# merch-hat.net
KiCad netlist of a schematic drawn in EAGLE
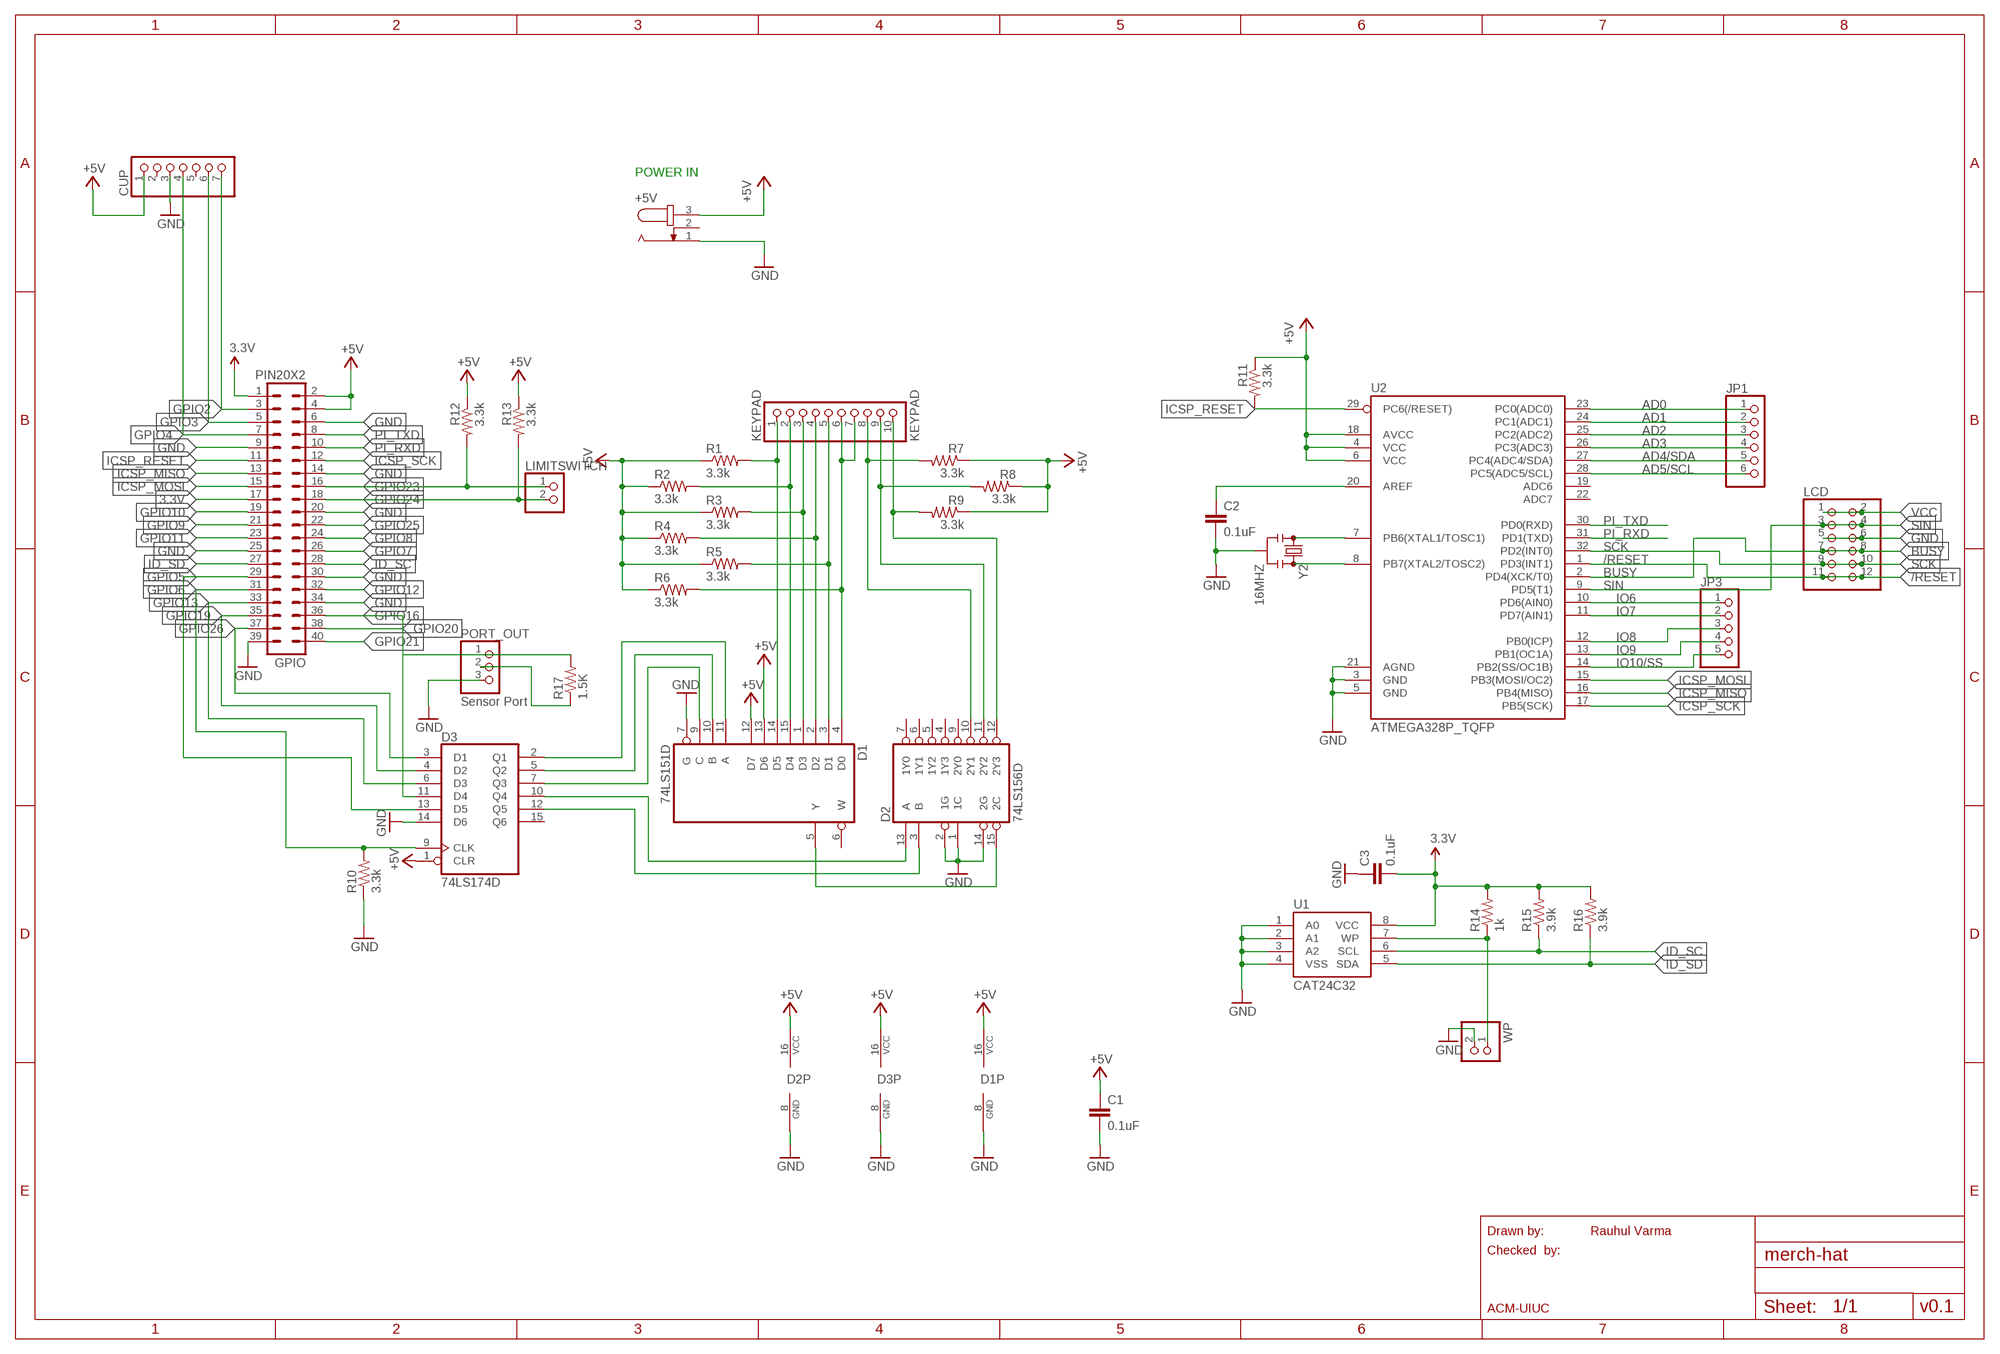
[diagram p0: schematic, sheet 1]

(export (version "E")
  (design (tool "Eeschema 10.0.6"))
  (components
    (comp (ref "+5V")
      (value "JACK-PLUG1")
      (footprint "eagle-import:SPC4078")
      (libsource (lib "eagle-import") (part "JACK-PLUG1"))
    )
    (comp (ref "C1")
      (value "0.1uF")
      (footprint "eagle-import:0603-CAP")
      (libsource (lib "eagle-import") (part "CAP0603-CAP"))
    )
    (comp (ref "C2")
      (value "0.1uF")
      (footprint "eagle-import:0603-CAP")
      (libsource (lib "eagle-import") (part "CAP0603-CAP"))
    )
    (comp (ref "C3")
      (value "0.1uF")
      (footprint "eagle-import:0603-CAP")
      (libsource (lib "eagle-import") (part "merch-hardware_CAP0603-CAP"))
    )
    (comp (ref "CUP")
      (value "PINHD-1X7")
      (footprint "eagle-import:1X07")
      (libsource (lib "eagle-import") (part "PINHD-1X7"))
    )
    (comp (ref "D1")
      (value "74LS151D")
      (footprint "eagle-import:SO16")
      (libsource (lib "eagle-import") (part "74151DLS"))
    )
    (comp (ref "D2")
      (value "74LS156D")
      (footprint "eagle-import:SO16")
      (libsource (lib "eagle-import") (part "74156DLS"))
    )
    (comp (ref "D3")
      (value "74LS174D")
      (footprint "eagle-import:SO16")
      (libsource (lib "eagle-import") (part "74174DLS"))
    )
    (comp (ref "GPIO")
      (value "PIN20X2")
      (footprint "eagle-import:PIN_20X2")
      (libsource (lib "eagle-import") (part "PIN20X2"))
    )
    (comp (ref "JP1")
      (value "PINHD-1X6")
      (footprint "eagle-import:1X06")
      (libsource (lib "eagle-import") (part "PINHD-1X6"))
    )
    (comp (ref "JP3")
      (value "PINHD-1X5")
      (footprint "eagle-import:1X05")
      (libsource (lib "eagle-import") (part "PINHD-1X5"))
    )
    (comp (ref "KEYPAD")
      (value "KEYPAD")
      (footprint "eagle-import:1X10")
      (libsource (lib "eagle-import") (part "PINHD-1X10"))
    )
    (comp (ref "LCD")
      (value "PINHD-2X6")
      (footprint "eagle-import:2X06")
      (libsource (lib "eagle-import") (part "PINHD-2X6"))
    )
    (comp (ref "LIMITSWITCH")
      (value "PINHD-1X2")
      (footprint "eagle-import:1X02")
      (libsource (lib "eagle-import") (part "PINHD-1X2"))
    )
    (comp (ref "PORT_OUT")
      (value "Sensor Port")
      (footprint "eagle-import:1X03")
      (libsource (lib "eagle-import") (part "PINHD-1X3"))
    )
    (comp (ref "R1")
      (value "3.3k")
      (footprint "eagle-import:0603-RES")
      (libsource (lib "eagle-import") (part "RESISTOR0603"))
    )
    (comp (ref "R2")
      (value "3.3k")
      (footprint "eagle-import:0603-RES")
      (libsource (lib "eagle-import") (part "RESISTOR0603"))
    )
    (comp (ref "R3")
      (value "3.3k")
      (footprint "eagle-import:0603-RES")
      (libsource (lib "eagle-import") (part "RESISTOR0603"))
    )
    (comp (ref "R4")
      (value "3.3k")
      (footprint "eagle-import:0603-RES")
      (libsource (lib "eagle-import") (part "RESISTOR0603"))
    )
    (comp (ref "R5")
      (value "3.3k")
      (footprint "eagle-import:0603-RES")
      (libsource (lib "eagle-import") (part "RESISTOR0603"))
    )
    (comp (ref "R6")
      (value "3.3k")
      (footprint "eagle-import:0603-RES")
      (libsource (lib "eagle-import") (part "RESISTOR0603"))
    )
    (comp (ref "R7")
      (value "3.3k")
      (footprint "eagle-import:0603-RES")
      (libsource (lib "eagle-import") (part "RESISTOR0603"))
    )
    (comp (ref "R8")
      (value "3.3k")
      (footprint "eagle-import:0603-RES")
      (libsource (lib "eagle-import") (part "RESISTOR0603"))
    )
    (comp (ref "R9")
      (value "3.3k")
      (footprint "eagle-import:0603-RES")
      (libsource (lib "eagle-import") (part "RESISTOR0603"))
    )
    (comp (ref "R10")
      (value "3.3k")
      (footprint "eagle-import:0603-RES")
      (libsource (lib "eagle-import") (part "RESISTOR0603"))
    )
    (comp (ref "R11")
      (value "3.3k")
      (footprint "eagle-import:0603-RES")
      (libsource (lib "eagle-import") (part "RESISTOR0603"))
    )
    (comp (ref "R12")
      (value "3.3k")
      (footprint "eagle-import:0603-RES")
      (libsource (lib "eagle-import") (part "RESISTOR0603"))
    )
    (comp (ref "R13")
      (value "3.3k")
      (footprint "eagle-import:0603-RES")
      (libsource (lib "eagle-import") (part "RESISTOR0603"))
    )
    (comp (ref "R14")
      (value "1k")
      (footprint "eagle-import:0603-RES")
      (libsource (lib "eagle-import") (part "RESISTOR0603-RES"))
    )
    (comp (ref "R15")
      (value "3.9k")
      (footprint "eagle-import:0603-RES")
      (libsource (lib "eagle-import") (part "RESISTOR0603-RES"))
    )
    (comp (ref "R16")
      (value "3.9k")
      (footprint "eagle-import:0603-RES")
      (libsource (lib "eagle-import") (part "RESISTOR0603-RES"))
    )
    (comp (ref "R17")
      (value "1.5K")
      (footprint "eagle-import:R0603")
      (libsource (lib "eagle-import") (part "R-US_R0603"))
    )
    (comp (ref "U1")
      (value "CAT24C32")
      (footprint "eagle-import:SO08")
      (libsource (lib "eagle-import") (part "CAT24C32"))
    )
    (comp (ref "U2")
      (value "ATMEGA328P_TQFP")
      (footprint "eagle-import:TQFP32-08")
      (libsource (lib "eagle-import") (part "ATMEGA328P_TQFP"))
    )
    (comp (ref "WP")
      (value "PINHD-1X2")
      (footprint "eagle-import:1X02")
      (libsource (lib "eagle-import") (part "PINHD-1X2"))
    )
    (comp (ref "Y2")
      (value "16MHZ")
      (footprint "eagle-import:RESONATOR-SMD")
      (libsource (lib "eagle-import") (part "RESONATOR16MHZ"))
    )
  )
  (nets
    (net (code "1") (name "+5V") (class "Default")
      (node (ref "+5V") (pin "3") (pinfunction "3_3") (pintype "passive"))
      (node (ref "C1") (pin "1") (pinfunction "1_1") (pintype "passive"))
      (node (ref "CUP") (pin "1") (pinfunction "1_1") (pintype "passive"))
      (node (ref "D1") (pin "12") (pinfunction "D7_12") (pintype "input"))
      (node (ref "D1") (pin "13") (pinfunction "D6_13") (pintype "input"))
      (node (ref "D1") (pin "16") (pinfunction "VCC_16") (pintype "power_in"))
      (node (ref "D2") (pin "16") (pinfunction "VCC_16") (pintype "power_in"))
      (node (ref "D3") (pin "1") (pinfunction "CLR_1") (pintype "input"))
      (node (ref "D3") (pin "16") (pinfunction "VCC_16") (pintype "power_in"))
      (node (ref "GPIO") (pin "2") (pinfunction "2_2") (pintype "passive"))
      (node (ref "GPIO") (pin "4") (pinfunction "4_4") (pintype "passive"))
      (node (ref "R1") (pin "1") (pinfunction "1_1") (pintype "passive"))
      (node (ref "R11") (pin "1") (pinfunction "1_1") (pintype "passive"))
      (node (ref "R12") (pin "1") (pinfunction "1_1") (pintype "passive"))
      (node (ref "R13") (pin "1") (pinfunction "1_1") (pintype "passive"))
      (node (ref "R2") (pin "1") (pinfunction "1_1") (pintype "passive"))
      (node (ref "R3") (pin "1") (pinfunction "1_1") (pintype "passive"))
      (node (ref "R4") (pin "1") (pinfunction "1_1") (pintype "passive"))
      (node (ref "R5") (pin "1") (pinfunction "1_1") (pintype "passive"))
      (node (ref "R6") (pin "1") (pinfunction "1_1") (pintype "passive"))
      (node (ref "R7") (pin "1") (pinfunction "1_1") (pintype "passive"))
      (node (ref "R8") (pin "1") (pinfunction "1_1") (pintype "passive"))
      (node (ref "R9") (pin "1") (pinfunction "1_1") (pintype "passive"))
      (node (ref "U2") (pin "18") (pinfunction "AVCC_18") (pintype "bidirectional"))
      (node (ref "U2") (pin "4") (pinfunction "VCC_4") (pintype "bidirectional"))
      (node (ref "U2") (pin "6") (pinfunction "VCC_6") (pintype "bidirectional"))
    )
    (net (code "2") (name "/AD0") (class "Default")
      (node (ref "JP1") (pin "1") (pinfunction "1_1") (pintype "passive"))
      (node (ref "U2") (pin "23") (pinfunction "PC0(ADC0)_23") (pintype "bidirectional"))
    )
    (net (code "3") (name "/AD1") (class "Default")
      (node (ref "JP1") (pin "2") (pinfunction "2_2") (pintype "passive"))
      (node (ref "U2") (pin "24") (pinfunction "PC1(ADC1)_24") (pintype "bidirectional"))
    )
    (net (code "4") (name "/AD2") (class "Default")
      (node (ref "JP1") (pin "3") (pinfunction "3_3") (pintype "passive"))
      (node (ref "U2") (pin "25") (pinfunction "PC2(ADC2)_25") (pintype "bidirectional"))
    )
    (net (code "5") (name "/AD3") (class "Default")
      (node (ref "JP1") (pin "4") (pinfunction "4_4") (pintype "passive"))
      (node (ref "U2") (pin "26") (pinfunction "PC3(ADC3)_26") (pintype "bidirectional"))
    )
    (net (code "6") (name "/AD4{slash}SDA") (class "Default")
      (node (ref "JP1") (pin "5") (pinfunction "5_5") (pintype "passive"))
      (node (ref "U2") (pin "27") (pinfunction "PC4(ADC4/SDA)_27") (pintype "bidirectional"))
    )
    (net (code "7") (name "/AD5{slash}SCL") (class "Default")
      (node (ref "JP1") (pin "6") (pinfunction "6_6") (pintype "passive"))
      (node (ref "U2") (pin "28") (pinfunction "PC5(ADC5/SCL)_28") (pintype "bidirectional"))
    )
    (net (code "8") (name "/IO6") (class "Default")
      (node (ref "JP3") (pin "1") (pinfunction "1_1") (pintype "passive"))
      (node (ref "U2") (pin "10") (pinfunction "PD6(AIN0)_10") (pintype "bidirectional"))
    )
    (net (code "9") (name "/IO7") (class "Default")
      (node (ref "JP3") (pin "2") (pinfunction "2_2") (pintype "passive"))
      (node (ref "U2") (pin "11") (pinfunction "PD7(AIN1)_11") (pintype "bidirectional"))
    )
    (net (code "10") (name "/IO8") (class "Default")
      (node (ref "JP3") (pin "3") (pinfunction "3_3") (pintype "passive"))
      (node (ref "U2") (pin "12") (pinfunction "PB0(ICP)_12") (pintype "bidirectional"))
    )
    (net (code "11") (name "/IO9") (class "Default")
      (node (ref "JP3") (pin "4") (pinfunction "4_4") (pintype "passive"))
      (node (ref "U2") (pin "13") (pinfunction "PB1(OC1A)_13") (pintype "bidirectional"))
    )
    (net (code "12") (name "/IO10{slash}SS") (class "Default")
      (node (ref "JP3") (pin "5") (pinfunction "5_5") (pintype "passive"))
      (node (ref "U2") (pin "14") (pinfunction "PB2(SS/OC1B)_14") (pintype "bidirectional"))
    )
    (net (code "13") (name "3.3V") (class "Default")
      (node (ref "C3") (pin "2") (pinfunction "2_2") (pintype "passive"))
      (node (ref "GPIO") (pin "1") (pinfunction "1_1") (pintype "passive"))
      (node (ref "GPIO") (pin "17") (pinfunction "17_17") (pintype "passive"))
      (node (ref "R14") (pin "2") (pinfunction "2_2") (pintype "passive"))
      (node (ref "R15") (pin "2") (pinfunction "2_2") (pintype "passive"))
      (node (ref "R16") (pin "2") (pinfunction "2_2") (pintype "passive"))
      (node (ref "U1") (pin "8") (pinfunction "VCC_8") (pintype "power_in"))
    )
    (net (code "14") (name "BUSY") (class "Default")
      (node (ref "LCD") (pin "7") (pinfunction "7_7") (pintype "passive"))
      (node (ref "LCD") (pin "8") (pinfunction "8_8") (pintype "passive"))
      (node (ref "U2") (pin "2") (pinfunction "PD4(XCK/T0)_2") (pintype "bidirectional"))
    )
    (net (code "15") (name "GND") (class "Default")
      (node (ref "+5V") (pin "1") (pinfunction "1_1") (pintype "passive"))
      (node (ref "C1") (pin "2") (pinfunction "2_2") (pintype "passive"))
      (node (ref "C2") (pin "2") (pinfunction "2_2") (pintype "passive"))
      (node (ref "C3") (pin "1") (pinfunction "1_1") (pintype "passive"))
      (node (ref "CUP") (pin "3") (pinfunction "3_3") (pintype "passive"))
      (node (ref "D1") (pin "7") (pinfunction "G_7") (pintype "input"))
      (node (ref "D1") (pin "8") (pinfunction "GND_8") (pintype "power_in"))
      (node (ref "D2") (pin "1") (pinfunction "1C_1") (pintype "input"))
      (node (ref "D2") (pin "14") (pinfunction "2G_14") (pintype "input"))
      (node (ref "D2") (pin "2") (pinfunction "1G_2") (pintype "input"))
      (node (ref "D2") (pin "8") (pinfunction "GND_8") (pintype "power_in"))
      (node (ref "D3") (pin "14") (pinfunction "D6_14") (pintype "input"))
      (node (ref "D3") (pin "8") (pinfunction "GND_8") (pintype "power_in"))
      (node (ref "GPIO") (pin "14") (pinfunction "14_14") (pintype "passive"))
      (node (ref "GPIO") (pin "20") (pinfunction "20_20") (pintype "passive"))
      (node (ref "GPIO") (pin "25") (pinfunction "25_25") (pintype "passive"))
      (node (ref "GPIO") (pin "30") (pinfunction "30_30") (pintype "passive"))
      (node (ref "GPIO") (pin "34") (pinfunction "34_34") (pintype "passive"))
      (node (ref "GPIO") (pin "39") (pinfunction "39_39") (pintype "passive"))
      (node (ref "GPIO") (pin "6") (pinfunction "6_6") (pintype "passive"))
      (node (ref "GPIO") (pin "9") (pinfunction "9_9") (pintype "passive"))
      (node (ref "LCD") (pin "5") (pinfunction "5_5") (pintype "passive"))
      (node (ref "LCD") (pin "6") (pinfunction "6_6") (pintype "passive"))
      (node (ref "PORT_OUT") (pin "3") (pinfunction "3_3") (pintype "passive"))
      (node (ref "R10") (pin "1") (pinfunction "1_1") (pintype "passive"))
      (node (ref "U1") (pin "1") (pinfunction "A0_1") (pintype "bidirectional"))
      (node (ref "U1") (pin "2") (pinfunction "A1_2") (pintype "bidirectional"))
      (node (ref "U1") (pin "3") (pinfunction "A2_3") (pintype "bidirectional"))
      (node (ref "U1") (pin "4") (pinfunction "VSS_4") (pintype "power_in"))
      (node (ref "U2") (pin "21") (pinfunction "AGND_21") (pintype "bidirectional"))
      (node (ref "U2") (pin "3") (pinfunction "GND_3") (pintype "bidirectional"))
      (node (ref "U2") (pin "5") (pinfunction "GND_5") (pintype "bidirectional"))
      (node (ref "WP") (pin "2") (pinfunction "2_2") (pintype "passive"))
      (node (ref "Y2") (pin "2") (pinfunction "2_2") (pintype "passive"))
    )
    (net (code "16") (name "GPIO2") (class "Default")
      (node (ref "CUP") (pin "7") (pinfunction "7_7") (pintype "passive"))
      (node (ref "GPIO") (pin "3") (pinfunction "3_3") (pintype "passive"))
    )
    (net (code "17") (name "GPIO3") (class "Default")
      (node (ref "CUP") (pin "6") (pinfunction "6_6") (pintype "passive"))
      (node (ref "GPIO") (pin "5") (pinfunction "5_5") (pintype "passive"))
    )
    (net (code "18") (name "GPIO4") (class "Default")
      (node (ref "CUP") (pin "4") (pinfunction "4_4") (pintype "passive"))
      (node (ref "GPIO") (pin "7") (pinfunction "7_7") (pintype "passive"))
    )
    (net (code "19") (name "GPIO5") (class "Default")
      (node (ref "D3") (pin "13") (pinfunction "D5_13") (pintype "input"))
      (node (ref "GPIO") (pin "29") (pinfunction "29_29") (pintype "passive"))
    )
    (net (code "20") (name "GPIO6") (class "Default")
      (node (ref "D3") (pin "9") (pinfunction "CLK_9") (pintype "input"))
      (node (ref "GPIO") (pin "31") (pinfunction "31_31") (pintype "passive"))
      (node (ref "R10") (pin "2") (pinfunction "2_2") (pintype "passive"))
    )
    (net (code "21") (name "GPIO7") (class "Default")
      (node (ref "GPIO") (pin "26") (pinfunction "26_26") (pintype "passive"))
    )
    (net (code "22") (name "GPIO8") (class "Default")
      (node (ref "GPIO") (pin "24") (pinfunction "24_24") (pintype "passive"))
    )
    (net (code "23") (name "GPIO9") (class "Default")
      (node (ref "GPIO") (pin "21") (pinfunction "21_21") (pintype "passive"))
    )
    (net (code "24") (name "GPIO10") (class "Default")
      (node (ref "GPIO") (pin "19") (pinfunction "19_19") (pintype "passive"))
    )
    (net (code "25") (name "GPIO11") (class "Default")
      (node (ref "GPIO") (pin "23") (pinfunction "23_23") (pintype "passive"))
    )
    (net (code "26") (name "GPIO12") (class "Default")
      (node (ref "GPIO") (pin "32") (pinfunction "32_32") (pintype "passive"))
    )
    (net (code "27") (name "GPIO13") (class "Default")
      (node (ref "D3") (pin "6") (pinfunction "D3_6") (pintype "input"))
      (node (ref "GPIO") (pin "33") (pinfunction "33_33") (pintype "passive"))
    )
    (net (code "28") (name "GPIO16") (class "Default")
      (node (ref "D3") (pin "11") (pinfunction "D4_11") (pintype "input"))
      (node (ref "GPIO") (pin "36") (pinfunction "36_36") (pintype "passive"))
    )
    (net (code "29") (name "GPIO19") (class "Default")
      (node (ref "D3") (pin "4") (pinfunction "D2_4") (pintype "input"))
      (node (ref "GPIO") (pin "35") (pinfunction "35_35") (pintype "passive"))
    )
    (net (code "30") (name "GPIO20") (class "Default")
      (node (ref "GPIO") (pin "38") (pinfunction "38_38") (pintype "passive"))
      (node (ref "PORT_OUT") (pin "1") (pinfunction "1_1") (pintype "passive"))
      (node (ref "R17") (pin "2") (pinfunction "2_2") (pintype "passive"))
    )
    (net (code "31") (name "GPIO21") (class "Default")
      (node (ref "GPIO") (pin "40") (pinfunction "40_40") (pintype "passive"))
    )
    (net (code "32") (name "GPIO23") (class "Default")
      (node (ref "GPIO") (pin "16") (pinfunction "16_16") (pintype "passive"))
      (node (ref "LIMITSWITCH") (pin "1") (pinfunction "1_1") (pintype "passive"))
      (node (ref "R12") (pin "2") (pinfunction "2_2") (pintype "passive"))
    )
    (net (code "33") (name "GPIO24") (class "Default")
      (node (ref "GPIO") (pin "18") (pinfunction "18_18") (pintype "passive"))
      (node (ref "LIMITSWITCH") (pin "2") (pinfunction "2_2") (pintype "passive"))
      (node (ref "R13") (pin "2") (pinfunction "2_2") (pintype "passive"))
    )
    (net (code "34") (name "GPIO25") (class "Default")
      (node (ref "GPIO") (pin "22") (pinfunction "22_22") (pintype "passive"))
    )
    (net (code "35") (name "GPIO26") (class "Default")
      (node (ref "D3") (pin "3") (pinfunction "D1_3") (pintype "input"))
      (node (ref "GPIO") (pin "37") (pinfunction "37_37") (pintype "passive"))
    )
    (net (code "36") (name "ICSP_MISO") (class "Default")
      (node (ref "GPIO") (pin "13") (pinfunction "13_13") (pintype "passive"))
      (node (ref "U2") (pin "16") (pinfunction "PB4(MISO)_16") (pintype "bidirectional"))
    )
    (net (code "37") (name "ICSP_MOSI") (class "Default")
      (node (ref "GPIO") (pin "15") (pinfunction "15_15") (pintype "passive"))
      (node (ref "U2") (pin "15") (pinfunction "PB3(MOSI/OC2)_15") (pintype "bidirectional"))
    )
    (net (code "38") (name "ICSP_RESET") (class "Default")
      (node (ref "GPIO") (pin "11") (pinfunction "11_11") (pintype "passive"))
      (node (ref "R11") (pin "2") (pinfunction "2_2") (pintype "passive"))
      (node (ref "U2") (pin "29") (pinfunction "PC6(/RESET)_29") (pintype "bidirectional"))
    )
    (net (code "39") (name "ICSP_SCK") (class "Default")
      (node (ref "GPIO") (pin "12") (pinfunction "12_12") (pintype "passive"))
      (node (ref "U2") (pin "17") (pinfunction "PB5(SCK)_17") (pintype "bidirectional"))
    )
    (net (code "40") (name "ID_SC") (class "Default")
      (node (ref "GPIO") (pin "28") (pinfunction "28_28") (pintype "passive"))
      (node (ref "R15") (pin "1") (pinfunction "1_1") (pintype "passive"))
      (node (ref "U1") (pin "6") (pinfunction "SCL_6") (pintype "bidirectional"))
    )
    (net (code "41") (name "ID_SD") (class "Default")
      (node (ref "GPIO") (pin "27") (pinfunction "27_27") (pintype "passive"))
      (node (ref "R16") (pin "1") (pinfunction "1_1") (pintype "passive"))
      (node (ref "U1") (pin "5") (pinfunction "SDA_5") (pintype "bidirectional"))
    )
    (net (code "42") (name "Net-(D1A-A)") (class "Default")
      (node (ref "D1") (pin "11") (pinfunction "A_11") (pintype "input"))
      (node (ref "D3") (pin "2") (pinfunction "Q1_2") (pintype "output"))
    )
    (net (code "43") (name "Net-(D1A-B)") (class "Default")
      (node (ref "D1") (pin "10") (pinfunction "B_10") (pintype "input"))
      (node (ref "D3") (pin "5") (pinfunction "Q2_5") (pintype "output"))
    )
    (net (code "44") (name "Net-(D1A-C)") (class "Default")
      (node (ref "D1") (pin "9") (pinfunction "C_9") (pintype "input"))
      (node (ref "D3") (pin "7") (pinfunction "Q3_7") (pintype "output"))
    )
    (net (code "45") (name "Net-(D1A-D0)") (class "Default")
      (node (ref "D1") (pin "4") (pinfunction "D0_4") (pintype "input"))
      (node (ref "KEYPAD") (pin "6") (pinfunction "6_6") (pintype "passive"))
      (node (ref "KEYPAD") (pin "7") (pinfunction "7_7") (pintype "passive"))
      (node (ref "R6") (pin "2") (pinfunction "2_2") (pintype "passive"))
    )
    (net (code "46") (name "Net-(D1A-D1)") (class "Default")
      (node (ref "D1") (pin "3") (pinfunction "D1_3") (pintype "input"))
      (node (ref "KEYPAD") (pin "5") (pinfunction "5_5") (pintype "passive"))
      (node (ref "R5") (pin "2") (pinfunction "2_2") (pintype "passive"))
    )
    (net (code "47") (name "Net-(D1A-D2)") (class "Default")
      (node (ref "D1") (pin "2") (pinfunction "D2_2") (pintype "input"))
      (node (ref "KEYPAD") (pin "4") (pinfunction "4_4") (pintype "passive"))
      (node (ref "R4") (pin "2") (pinfunction "2_2") (pintype "passive"))
    )
    (net (code "48") (name "Net-(D1A-D3)") (class "Default")
      (node (ref "D1") (pin "1") (pinfunction "D3_1") (pintype "input"))
      (node (ref "KEYPAD") (pin "3") (pinfunction "3_3") (pintype "passive"))
      (node (ref "R3") (pin "2") (pinfunction "2_2") (pintype "passive"))
    )
    (net (code "49") (name "Net-(D1A-D4)") (class "Default")
      (node (ref "D1") (pin "15") (pinfunction "D4_15") (pintype "input"))
      (node (ref "KEYPAD") (pin "2") (pinfunction "2_2") (pintype "passive"))
      (node (ref "R2") (pin "2") (pinfunction "2_2") (pintype "passive"))
    )
    (net (code "50") (name "Net-(D1A-D5)") (class "Default")
      (node (ref "D1") (pin "14") (pinfunction "D5_14") (pintype "input"))
      (node (ref "KEYPAD") (pin "1") (pinfunction "1_1") (pintype "passive"))
      (node (ref "R1") (pin "2") (pinfunction "2_2") (pintype "passive"))
    )
    (net (code "51") (name "Net-(D1A-Y)") (class "Default")
      (node (ref "D1") (pin "5") (pinfunction "Y_5") (pintype "output"))
      (node (ref "D2") (pin "15") (pinfunction "2C_15") (pintype "input"))
    )
    (net (code "52") (name "Net-(D2A-2Y1)") (class "Default")
      (node (ref "D2") (pin "10") (pinfunction "2Y1_10") (pintype "open_collector"))
      (node (ref "KEYPAD") (pin "8") (pinfunction "8_8") (pintype "passive"))
      (node (ref "R7") (pin "2") (pinfunction "2_2") (pintype "passive"))
    )
    (net (code "53") (name "Net-(D2A-2Y2)") (class "Default")
      (node (ref "D2") (pin "11") (pinfunction "2Y2_11") (pintype "open_collector"))
      (node (ref "KEYPAD") (pin "9") (pinfunction "9_9") (pintype "passive"))
      (node (ref "R8") (pin "2") (pinfunction "2_2") (pintype "passive"))
    )
    (net (code "54") (name "Net-(D2A-2Y3)") (class "Default")
      (node (ref "D2") (pin "12") (pinfunction "2Y3_12") (pintype "open_collector"))
      (node (ref "KEYPAD") (pin "10") (pinfunction "10_10") (pintype "passive"))
      (node (ref "R9") (pin "2") (pinfunction "2_2") (pintype "passive"))
    )
    (net (code "55") (name "Net-(D2A-A)") (class "Default")
      (node (ref "D2") (pin "13") (pinfunction "A_13") (pintype "input"))
      (node (ref "D3") (pin "10") (pinfunction "Q4_10") (pintype "output"))
    )
    (net (code "56") (name "Net-(D2A-B)") (class "Default")
      (node (ref "D2") (pin "3") (pinfunction "B_3") (pintype "input"))
      (node (ref "D3") (pin "12") (pinfunction "Q5_12") (pintype "output"))
    )
    (net (code "57") (name "Net-(PORT_OUT-Pad2)") (class "Default")
      (node (ref "PORT_OUT") (pin "2") (pinfunction "2_2") (pintype "passive"))
      (node (ref "R17") (pin "1") (pinfunction "1_1") (pintype "passive"))
    )
    (net (code "58") (name "Net-(U1-WP)") (class "Default")
      (node (ref "R14") (pin "1") (pinfunction "1_1") (pintype "passive"))
      (node (ref "U1") (pin "7") (pinfunction "WP_7") (pintype "bidirectional"))
      (node (ref "WP") (pin "1") (pinfunction "1_1") (pintype "passive"))
    )
    (net (code "59") (name "Net-(U2-AREF)") (class "Default")
      (node (ref "C2") (pin "1") (pinfunction "1_1") (pintype "passive"))
      (node (ref "U2") (pin "20") (pinfunction "AREF_20") (pintype "bidirectional"))
    )
    (net (code "60") (name "Net-(U2-PB6(XTAL1{slash}TOSC1))") (class "Default")
      (node (ref "U2") (pin "7") (pinfunction "PB6(XTAL1/TOSC1)_7") (pintype "bidirectional"))
      (node (ref "Y2") (pin "1") (pinfunction "1_1") (pintype "passive"))
    )
    (net (code "61") (name "Net-(U2-PB7(XTAL2{slash}TOSC2))") (class "Default")
      (node (ref "U2") (pin "8") (pinfunction "PB7(XTAL2/TOSC2)_8") (pintype "bidirectional"))
      (node (ref "Y2") (pin "3") (pinfunction "3_3") (pintype "passive"))
    )
    (net (code "62") (name "PI_RXD") (class "Default")
      (node (ref "GPIO") (pin "10") (pinfunction "10_10") (pintype "passive"))
      (node (ref "U2") (pin "31") (pinfunction "PD1(TXD)_31") (pintype "bidirectional"))
    )
    (net (code "63") (name "PI_TXD") (class "Default")
      (node (ref "GPIO") (pin "8") (pinfunction "8_8") (pintype "passive"))
      (node (ref "U2") (pin "30") (pinfunction "PD0(RXD)_30") (pintype "bidirectional"))
    )
    (net (code "64") (name "SCK") (class "Default")
      (node (ref "LCD") (pin "10") (pinfunction "10_10") (pintype "passive"))
      (node (ref "LCD") (pin "9") (pinfunction "9_9") (pintype "passive"))
      (node (ref "U2") (pin "32") (pinfunction "PD2(INT0)_32") (pintype "bidirectional"))
    )
    (net (code "65") (name "SIN") (class "Default")
      (node (ref "LCD") (pin "3") (pinfunction "3_3") (pintype "passive"))
      (node (ref "LCD") (pin "4") (pinfunction "4_4") (pintype "passive"))
      (node (ref "U2") (pin "9") (pinfunction "PD5(T1)_9") (pintype "bidirectional"))
    )
    (net (code "66") (name "VCC") (class "Default")
      (node (ref "LCD") (pin "1") (pinfunction "1_1") (pintype "passive"))
      (node (ref "LCD") (pin "2") (pinfunction "2_2") (pintype "passive"))
    )
    (net (code "67") (name "unconnected-(+5V-Pad2)") (class "Default")
      (node (ref "+5V") (pin "2") (pinfunction "2_2") (pintype "passive"))
    )
    (net (code "68") (name "unconnected-(CUP-Pad2)") (class "Default")
      (node (ref "CUP") (pin "2") (pinfunction "2_2") (pintype "passive"))
    )
    (net (code "69") (name "unconnected-(CUP-Pad5)") (class "Default")
      (node (ref "CUP") (pin "5") (pinfunction "5_5") (pintype "passive"))
    )
    (net (code "70") (name "unconnected-(D1A-W-Pad6)") (class "Default")
      (node (ref "D1") (pin "6") (pinfunction "W_6") (pintype "output"))
    )
    (net (code "71") (name "unconnected-(D2A-1Y0-Pad7)") (class "Default")
      (node (ref "D2") (pin "7") (pinfunction "1Y0_7") (pintype "open_collector"))
    )
    (net (code "72") (name "unconnected-(D2A-1Y1-Pad6)") (class "Default")
      (node (ref "D2") (pin "6") (pinfunction "1Y1_6") (pintype "open_collector"))
    )
    (net (code "73") (name "unconnected-(D2A-1Y2-Pad5)") (class "Default")
      (node (ref "D2") (pin "5") (pinfunction "1Y2_5") (pintype "open_collector"))
    )
    (net (code "74") (name "unconnected-(D2A-1Y3-Pad4)") (class "Default")
      (node (ref "D2") (pin "4") (pinfunction "1Y3_4") (pintype "open_collector"))
    )
    (net (code "75") (name "unconnected-(D2A-2Y0-Pad9)") (class "Default")
      (node (ref "D2") (pin "9") (pinfunction "2Y0_9") (pintype "open_collector"))
    )
    (net (code "76") (name "unconnected-(D3A-Q6-Pad15)") (class "Default")
      (node (ref "D3") (pin "15") (pinfunction "Q6_15") (pintype "output"))
    )
    (net (code "77") (name "unconnected-(U2-ADC6-Pad19)") (class "Default")
      (node (ref "U2") (pin "19") (pinfunction "ADC6_19") (pintype "bidirectional"))
    )
    (net (code "78") (name "unconnected-(U2-ADC7-Pad22)") (class "Default")
      (node (ref "U2") (pin "22") (pinfunction "ADC7_22") (pintype "bidirectional"))
    )
    (net (code "79") (name "{slash}RESET") (class "Default")
      (node (ref "LCD") (pin "11") (pinfunction "11_11") (pintype "passive"))
      (node (ref "LCD") (pin "12") (pinfunction "12_12") (pintype "passive"))
      (node (ref "U2") (pin "1") (pinfunction "PD3(INT1)_1") (pintype "bidirectional"))
    )
  )
)
